# Main.net
KiCad netlist of a schematic drawn in Altium Designer
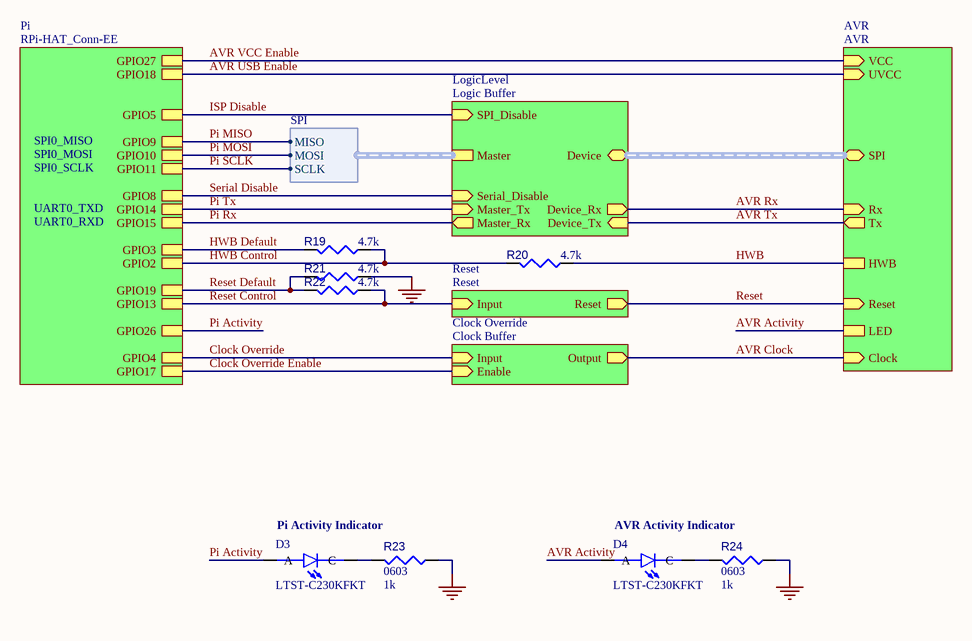
[diagram p0: Main.SchDoc]

(export (version "E")
  (design (tool "Eeschema 10.0.6"))
  (components
    (comp (ref "D3")
      (value "LTST-C230KFKT")
      (footprint "LEDC3216X110")
      (description "Orange 605nm LED Indication - Discrete 2V 1206 (3216 Metric)")
      (fields (field (name "MF") "Lite-On Inc."))
      (libsource (lib "Twill Technology Inc") (part "LTST-C230KFKT"))
    )
    (comp (ref "D4")
      (value "LTST-C230KFKT")
      (footprint "LEDC3216X110")
      (description "Orange 605nm LED Indication - Discrete 2V 1206 (3216 Metric)")
      (fields (field (name "MF") "Lite-On Inc."))
      (libsource (lib "Twill Technology Inc") (part "LTST-C230KFKT"))
    )
    (comp (ref "R19")
      (value "4.7k")
      (footprint "RESC1608X55X25ML10T15")
      (description "Chip Resistor, 1 KOhm, +/-1%, 0.1 W, -55 to 155 degC, 0603 (1608 Metric)")
      (fields (field (name "POWER") "100mW") (field (name "TOLERANCE") "1%"))
      (libsource (lib "Twill Technology Inc") (part "RES-2"))
    )
    (comp (ref "R20")
      (value "4.7k")
      (footprint "RESC1608X55X25ML10T15")
      (description "Chip Resistor, 1 KOhm, +/-1%, 0.1 W, -55 to 155 degC, 0603 (1608 Metric)")
      (fields (field (name "POWER") "100mW") (field (name "TOLERANCE") "1%"))
      (libsource (lib "Twill Technology Inc") (part "RES-2"))
    )
    (comp (ref "R21")
      (value "4.7k")
      (footprint "RESC1608X55X25ML10T15")
      (description "Chip Resistor, 1 KOhm, +/-1%, 0.1 W, -55 to 155 degC, 0603 (1608 Metric)")
      (fields (field (name "POWER") "100mW") (field (name "TOLERANCE") "1%"))
      (libsource (lib "Twill Technology Inc") (part "RES-2"))
    )
    (comp (ref "R22")
      (value "4.7k")
      (footprint "RESC1608X55X25ML10T15")
      (description "Chip Resistor, 1 KOhm, +/-1%, 0.1 W, -55 to 155 degC, 0603 (1608 Metric)")
      (fields (field (name "POWER") "100mW") (field (name "TOLERANCE") "1%"))
      (libsource (lib "Twill Technology Inc") (part "RES-2"))
    )
    (comp (ref "R23")
      (value "1k")
      (footprint "RESC1608X55X25ML10T15")
      (description "Chip Resistor, 1 KOhm, +/-1%, 0.1 W, -55 to 155 degC, 0603 (1608 Metric)")
      (fields
        (field (name "CASE/PACKAGE") "0603")
        (field (name "POWER") "100mW")
        (field (name "TOLERANCE") "1%")
      )
      (libsource (lib "Twill Technology Inc") (part "RES-2"))
    )
    (comp (ref "R24")
      (value "1k")
      (footprint "RESC1608X55X25ML10T15")
      (description "Chip Resistor, 1 KOhm, +/-1%, 0.1 W, -55 to 155 degC, 0603 (1608 Metric)")
      (fields
        (field (name "CASE/PACKAGE") "0603")
        (field (name "POWER") "100mW")
        (field (name "TOLERANCE") "1%")
      )
      (libsource (lib "Twill Technology Inc") (part "RES-2"))
    )
  )
  (nets
    (net (code "2") (name "/AVR Activity") (class "Default")
      (node (ref "D4") (pin "A") (pinfunction "A_A") (pintype "passive"))
    )
    (net (code "11") (name "/HWB") (class "Default")
      (node (ref "R20") (pin "1") (pinfunction "1_1") (pintype "passive"))
    )
    (net (code "12") (name "/HWB Control") (class "Default")
      (node (ref "R19") (pin "1") (pinfunction "1_1") (pintype "passive"))
      (node (ref "R20") (pin "2") (pinfunction "2_2") (pintype "passive"))
    )
    (net (code "13") (name "/HWB Default") (class "Default")
      (node (ref "R19") (pin "2") (pinfunction "2_2") (pintype "passive"))
    )
    (net (code "15") (name "/Pi Activity") (class "Default")
      (node (ref "D3") (pin "A") (pinfunction "A_A") (pintype "passive"))
    )
    (net (code "22") (name "/Reset Control") (class "Default")
      (node (ref "R22") (pin "1") (pinfunction "1_1") (pintype "passive"))
    )
    (net (code "23") (name "/Reset Default") (class "Default")
      (node (ref "R21") (pin "2") (pinfunction "2_2") (pintype "passive"))
      (node (ref "R22") (pin "2") (pinfunction "2_2") (pintype "passive"))
    )
    (net (code "26") (name "GND") (class "Default")
      (node (ref "R21") (pin "1") (pinfunction "1_1") (pintype "passive"))
      (node (ref "R23") (pin "1") (pinfunction "1_1") (pintype "passive"))
      (node (ref "R24") (pin "1") (pinfunction "1_1") (pintype "passive"))
    )
    (net (code "27") (name "Net-(D3-PadC)") (class "Default")
      (node (ref "D3") (pin "C") (pinfunction "C_C") (pintype "passive"))
      (node (ref "R23") (pin "2") (pinfunction "2_2") (pintype "passive"))
    )
    (net (code "28") (name "Net-(D4-PadC)") (class "Default")
      (node (ref "D4") (pin "C") (pinfunction "C_C") (pintype "passive"))
      (node (ref "R24") (pin "2") (pinfunction "2_2") (pintype "passive"))
    )
  )
)
